# CT310_V1_0.net
KiCad netlist of a schematic drawn in Altium Designer
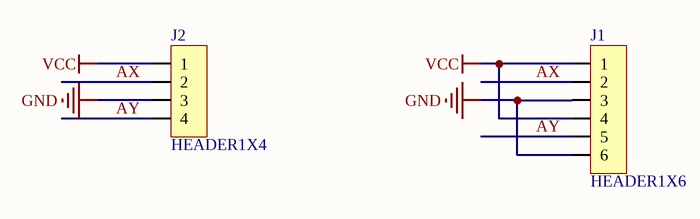
[diagram p0: CT310高端控制盒左摇杆电路V1.0.SchDoc]

(export (version "E")
  (design (tool "Eeschema 10.0.6"))
  (components
    (comp (ref "J1")
      (value "HEADER1X6")
      (footprint "H20JH")
      (libsource (lib "Connector Class") (part "HEADER1X6"))
    )
    (comp (ref "J2")
      (value "HEADER1X4")
      (footprint "ZH1X4WT-1.5")
      (libsource (lib "Connector Class") (part "HEADER1X4"))
    )
  )
  (nets
    (net (code "1") (name "/AX") (class "Default")
      (node (ref "J1") (pin "2") (pinfunction "2_2") (pintype "passive"))
      (node (ref "J2") (pin "2") (pinfunction "2_2") (pintype "passive"))
    )
    (net (code "2") (name "/AY") (class "Default")
      (node (ref "J1") (pin "5") (pinfunction "5_5") (pintype "passive"))
      (node (ref "J2") (pin "4") (pinfunction "4_4") (pintype "passive"))
    )
    (net (code "3") (name "GND") (class "Default")
      (node (ref "J1") (pin "3") (pinfunction "3_3") (pintype "passive"))
      (node (ref "J1") (pin "6") (pinfunction "6_6") (pintype "passive"))
      (node (ref "J2") (pin "3") (pinfunction "3_3") (pintype "passive"))
    )
    (net (code "4") (name "VCC") (class "Default")
      (node (ref "J1") (pin "1") (pinfunction "1_1") (pintype "passive"))
      (node (ref "J1") (pin "4") (pinfunction "4_4") (pintype "passive"))
      (node (ref "J2") (pin "1") (pinfunction "1_1") (pintype "passive"))
    )
  )
)
